# PWM_Generator.net
KiCad netlist of a schematic drawn in Altium Designer
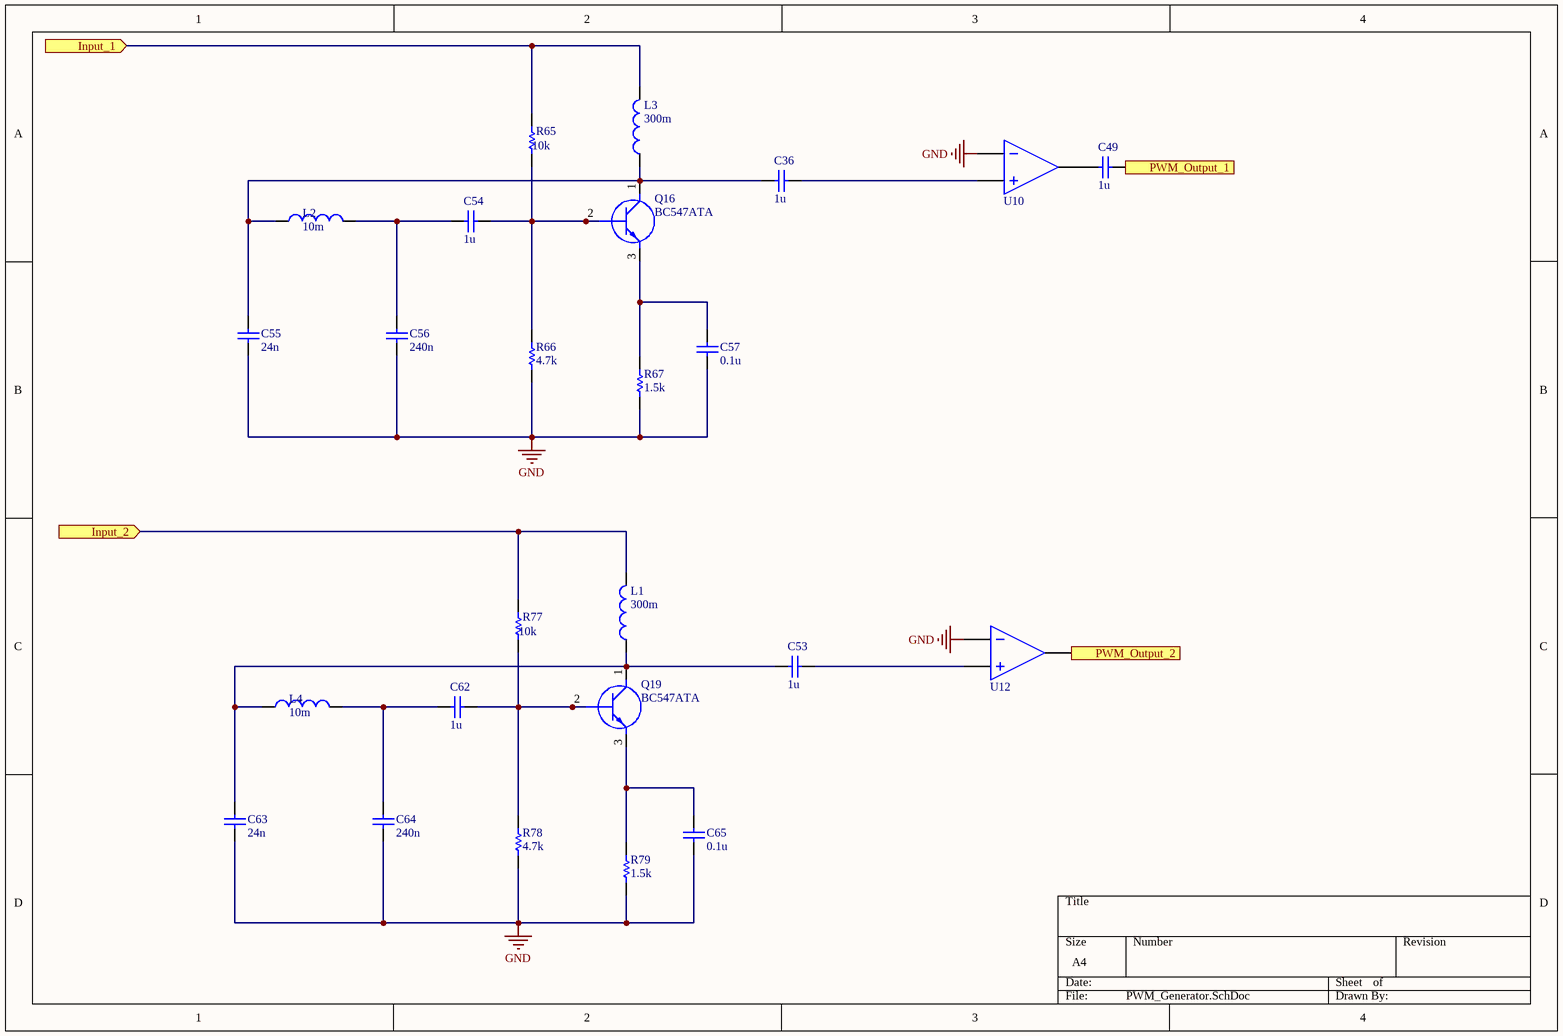
[diagram p0: PWM_Generator.SchDoc]

(export (version "E")
  (design (tool "Eeschema 10.0.6"))
  (components
    (comp (ref "C36")
      (value "1u")
      (description "Capacitor")
      (libsource (lib "Simulation Generic Components") (part "Capacitor"))
    )
    (comp (ref "C49")
      (value "1u")
      (description "Capacitor")
      (libsource (lib "Simulation Generic Components") (part "Capacitor"))
    )
    (comp (ref "C53")
      (value "1u")
      (description "Capacitor")
      (libsource (lib "Simulation Generic Components") (part "Capacitor"))
    )
    (comp (ref "C54")
      (value "1u")
      (description "Capacitor")
      (libsource (lib "Simulation Generic Components") (part "Capacitor"))
    )
    (comp (ref "C55")
      (value "24n")
      (description "Capacitor")
      (libsource (lib "Simulation Generic Components") (part "Capacitor"))
    )
    (comp (ref "C56")
      (value "240n")
      (description "Capacitor")
      (libsource (lib "Simulation Generic Components") (part "Capacitor"))
    )
    (comp (ref "C57")
      (value "0.1u")
      (description "Capacitor")
      (libsource (lib "Simulation Generic Components") (part "Capacitor"))
    )
    (comp (ref "C62")
      (value "1u")
      (description "Capacitor")
      (libsource (lib "Simulation Generic Components") (part "Capacitor"))
    )
    (comp (ref "C63")
      (value "24n")
      (description "Capacitor")
      (libsource (lib "Simulation Generic Components") (part "Capacitor"))
    )
    (comp (ref "C64")
      (value "240n")
      (description "Capacitor")
      (libsource (lib "Simulation Generic Components") (part "Capacitor"))
    )
    (comp (ref "C65")
      (value "0.1u")
      (description "Capacitor")
      (libsource (lib "Simulation Generic Components") (part "Capacitor"))
    )
    (comp (ref "L1")
      (value "300m")
      (description "Inductor")
      (libsource (lib "Simulation Generic Components") (part "Inductor"))
    )
    (comp (ref "L2")
      (value "10m")
      (description "Inductor")
      (libsource (lib "Simulation Generic Components") (part "Inductor"))
    )
    (comp (ref "L3")
      (value "300m")
      (description "Inductor")
      (libsource (lib "Simulation Generic Components") (part "Inductor"))
    )
    (comp (ref "L4")
      (value "10m")
      (description "Inductor")
      (libsource (lib "Simulation Generic Components") (part "Inductor"))
    )
    (comp (ref "Q16")
      (value "BC547ATA")
      (footprint "SamacSys:TO-92_(TO-226)")
      (description "Transistor BJT NPN")
      (fields (field (name "MOUSER PART NUMBER") "512-BC547ATA"))
      (libsource (lib "*") (part "BC547ATA"))
    )
    (comp (ref "Q19")
      (value "BC547ATA")
      (footprint "SamacSys:TO-92_(TO-226)")
      (description "Transistor BJT NPN")
      (fields (field (name "MOUSER PART NUMBER") "512-BC547ATA"))
      (libsource (lib "*") (part "BC547ATA"))
    )
    (comp (ref "R65")
      (value "10k")
      (description "Resistor")
      (libsource (lib "Simulation Generic Components") (part "Resistor"))
    )
    (comp (ref "R66")
      (value "4.7k")
      (description "Resistor")
      (libsource (lib "Simulation Generic Components") (part "Resistor"))
    )
    (comp (ref "R67")
      (value "1.5k")
      (description "Resistor")
      (libsource (lib "Simulation Generic Components") (part "Resistor"))
    )
    (comp (ref "R77")
      (value "10k")
      (description "Resistor")
      (libsource (lib "Simulation Generic Components") (part "Resistor"))
    )
    (comp (ref "R78")
      (value "4.7k")
      (description "Resistor")
      (libsource (lib "Simulation Generic Components") (part "Resistor"))
    )
    (comp (ref "R79")
      (value "1.5k")
      (description "Resistor")
      (libsource (lib "Simulation Generic Components") (part "Resistor"))
    )
    (comp (ref "U10")
      (value "Ideal Comparator")
      (libsource (lib "Simulation Generic Components") (part "Comparator"))
    )
    (comp (ref "U12")
      (value "Ideal Comparator")
      (libsource (lib "Simulation Generic Components") (part "Comparator"))
    )
  )
  (nets
    (net (code "1") (name "/Input_1") (class "Default")
      (node (ref "L3") (pin "2") (pinfunction "2_2") (pintype "passive"))
      (node (ref "R65") (pin "2") (pinfunction "2_2") (pintype "passive"))
    )
    (net (code "2") (name "/Input_2") (class "Default")
      (node (ref "L1") (pin "2") (pinfunction "2_2") (pintype "passive"))
      (node (ref "R77") (pin "2") (pinfunction "2_2") (pintype "passive"))
    )
    (net (code "3") (name "/PWM_Output_1") (class "Default")
      (node (ref "C49") (pin "2") (pinfunction "2_2") (pintype "passive"))
    )
    (net (code "4") (name "/PWM_Output_2") (class "Default")
      (node (ref "U12") (pin "3") (pinfunction "OUT_3") (pintype "passive"))
    )
    (net (code "5") (name "GND") (class "Default")
      (node (ref "C55") (pin "1") (pinfunction "1_1") (pintype "passive"))
      (node (ref "C56") (pin "1") (pinfunction "1_1") (pintype "passive"))
      (node (ref "C57") (pin "1") (pinfunction "1_1") (pintype "passive"))
      (node (ref "C63") (pin "1") (pinfunction "1_1") (pintype "passive"))
      (node (ref "C64") (pin "1") (pinfunction "1_1") (pintype "passive"))
      (node (ref "C65") (pin "1") (pinfunction "1_1") (pintype "passive"))
      (node (ref "R66") (pin "1") (pinfunction "1_1") (pintype "passive"))
      (node (ref "R67") (pin "1") (pinfunction "1_1") (pintype "passive"))
      (node (ref "R78") (pin "1") (pinfunction "1_1") (pintype "passive"))
      (node (ref "R79") (pin "1") (pinfunction "1_1") (pintype "passive"))
      (node (ref "U10") (pin "1") (pinfunction "IN-_1") (pintype "passive"))
      (node (ref "U12") (pin "1") (pinfunction "IN-_1") (pintype "passive"))
    )
    (net (code "6") (name "Net-(C54-Pad1)") (class "Default")
      (node (ref "C54") (pin "1") (pinfunction "1_1") (pintype "passive"))
      (node (ref "C56") (pin "2") (pinfunction "2_2") (pintype "passive"))
      (node (ref "L2") (pin "2") (pinfunction "2_2") (pintype "passive"))
    )
    (net (code "7") (name "Net-(C62-Pad1)") (class "Default")
      (node (ref "C62") (pin "1") (pinfunction "1_1") (pintype "passive"))
      (node (ref "C64") (pin "2") (pinfunction "2_2") (pintype "passive"))
      (node (ref "L4") (pin "2") (pinfunction "2_2") (pintype "passive"))
    )
    (net (code "8") (name "Net-(Q16-B)") (class "Default")
      (node (ref "C54") (pin "2") (pinfunction "2_2") (pintype "passive"))
      (node (ref "Q16") (pin "2") (pinfunction "B_2") (pintype "passive"))
      (node (ref "R65") (pin "1") (pinfunction "1_1") (pintype "passive"))
      (node (ref "R66") (pin "2") (pinfunction "2_2") (pintype "passive"))
    )
    (net (code "9") (name "Net-(Q16-C)") (class "Default")
      (node (ref "C36") (pin "1") (pinfunction "1_1") (pintype "passive"))
      (node (ref "C55") (pin "2") (pinfunction "2_2") (pintype "passive"))
      (node (ref "L2") (pin "1") (pinfunction "1_1") (pintype "passive"))
      (node (ref "L3") (pin "1") (pinfunction "1_1") (pintype "passive"))
      (node (ref "Q16") (pin "1") (pinfunction "C_1") (pintype "passive"))
    )
    (net (code "10") (name "Net-(Q16-E)") (class "Default")
      (node (ref "C57") (pin "2") (pinfunction "2_2") (pintype "passive"))
      (node (ref "Q16") (pin "3") (pinfunction "E_3") (pintype "passive"))
      (node (ref "R67") (pin "2") (pinfunction "2_2") (pintype "passive"))
    )
    (net (code "11") (name "Net-(Q19-B)") (class "Default")
      (node (ref "C62") (pin "2") (pinfunction "2_2") (pintype "passive"))
      (node (ref "Q19") (pin "2") (pinfunction "B_2") (pintype "passive"))
      (node (ref "R77") (pin "1") (pinfunction "1_1") (pintype "passive"))
      (node (ref "R78") (pin "2") (pinfunction "2_2") (pintype "passive"))
    )
    (net (code "12") (name "Net-(Q19-C)") (class "Default")
      (node (ref "C53") (pin "1") (pinfunction "1_1") (pintype "passive"))
      (node (ref "C63") (pin "2") (pinfunction "2_2") (pintype "passive"))
      (node (ref "L1") (pin "1") (pinfunction "1_1") (pintype "passive"))
      (node (ref "L4") (pin "1") (pinfunction "1_1") (pintype "passive"))
      (node (ref "Q19") (pin "1") (pinfunction "C_1") (pintype "passive"))
    )
    (net (code "13") (name "Net-(Q19-E)") (class "Default")
      (node (ref "C65") (pin "2") (pinfunction "2_2") (pintype "passive"))
      (node (ref "Q19") (pin "3") (pinfunction "E_3") (pintype "passive"))
      (node (ref "R79") (pin "2") (pinfunction "2_2") (pintype "passive"))
    )
    (net (code "14") (name "Net-(U10-IN+)") (class "Default")
      (node (ref "C36") (pin "2") (pinfunction "2_2") (pintype "passive"))
      (node (ref "U10") (pin "2") (pinfunction "IN+_2") (pintype "passive"))
    )
    (net (code "15") (name "Net-(U10-OUT)") (class "Default")
      (node (ref "C49") (pin "1") (pinfunction "1_1") (pintype "passive"))
      (node (ref "U10") (pin "3") (pinfunction "OUT_3") (pintype "passive"))
    )
    (net (code "16") (name "Net-(U12-IN+)") (class "Default")
      (node (ref "C53") (pin "2") (pinfunction "2_2") (pintype "passive"))
      (node (ref "U12") (pin "2") (pinfunction "IN+_2") (pintype "passive"))
    )
  )
)
